# Header_-_Digital_Pot_4131_with_Transisto.net
KiCad netlist of a schematic drawn in EAGLE
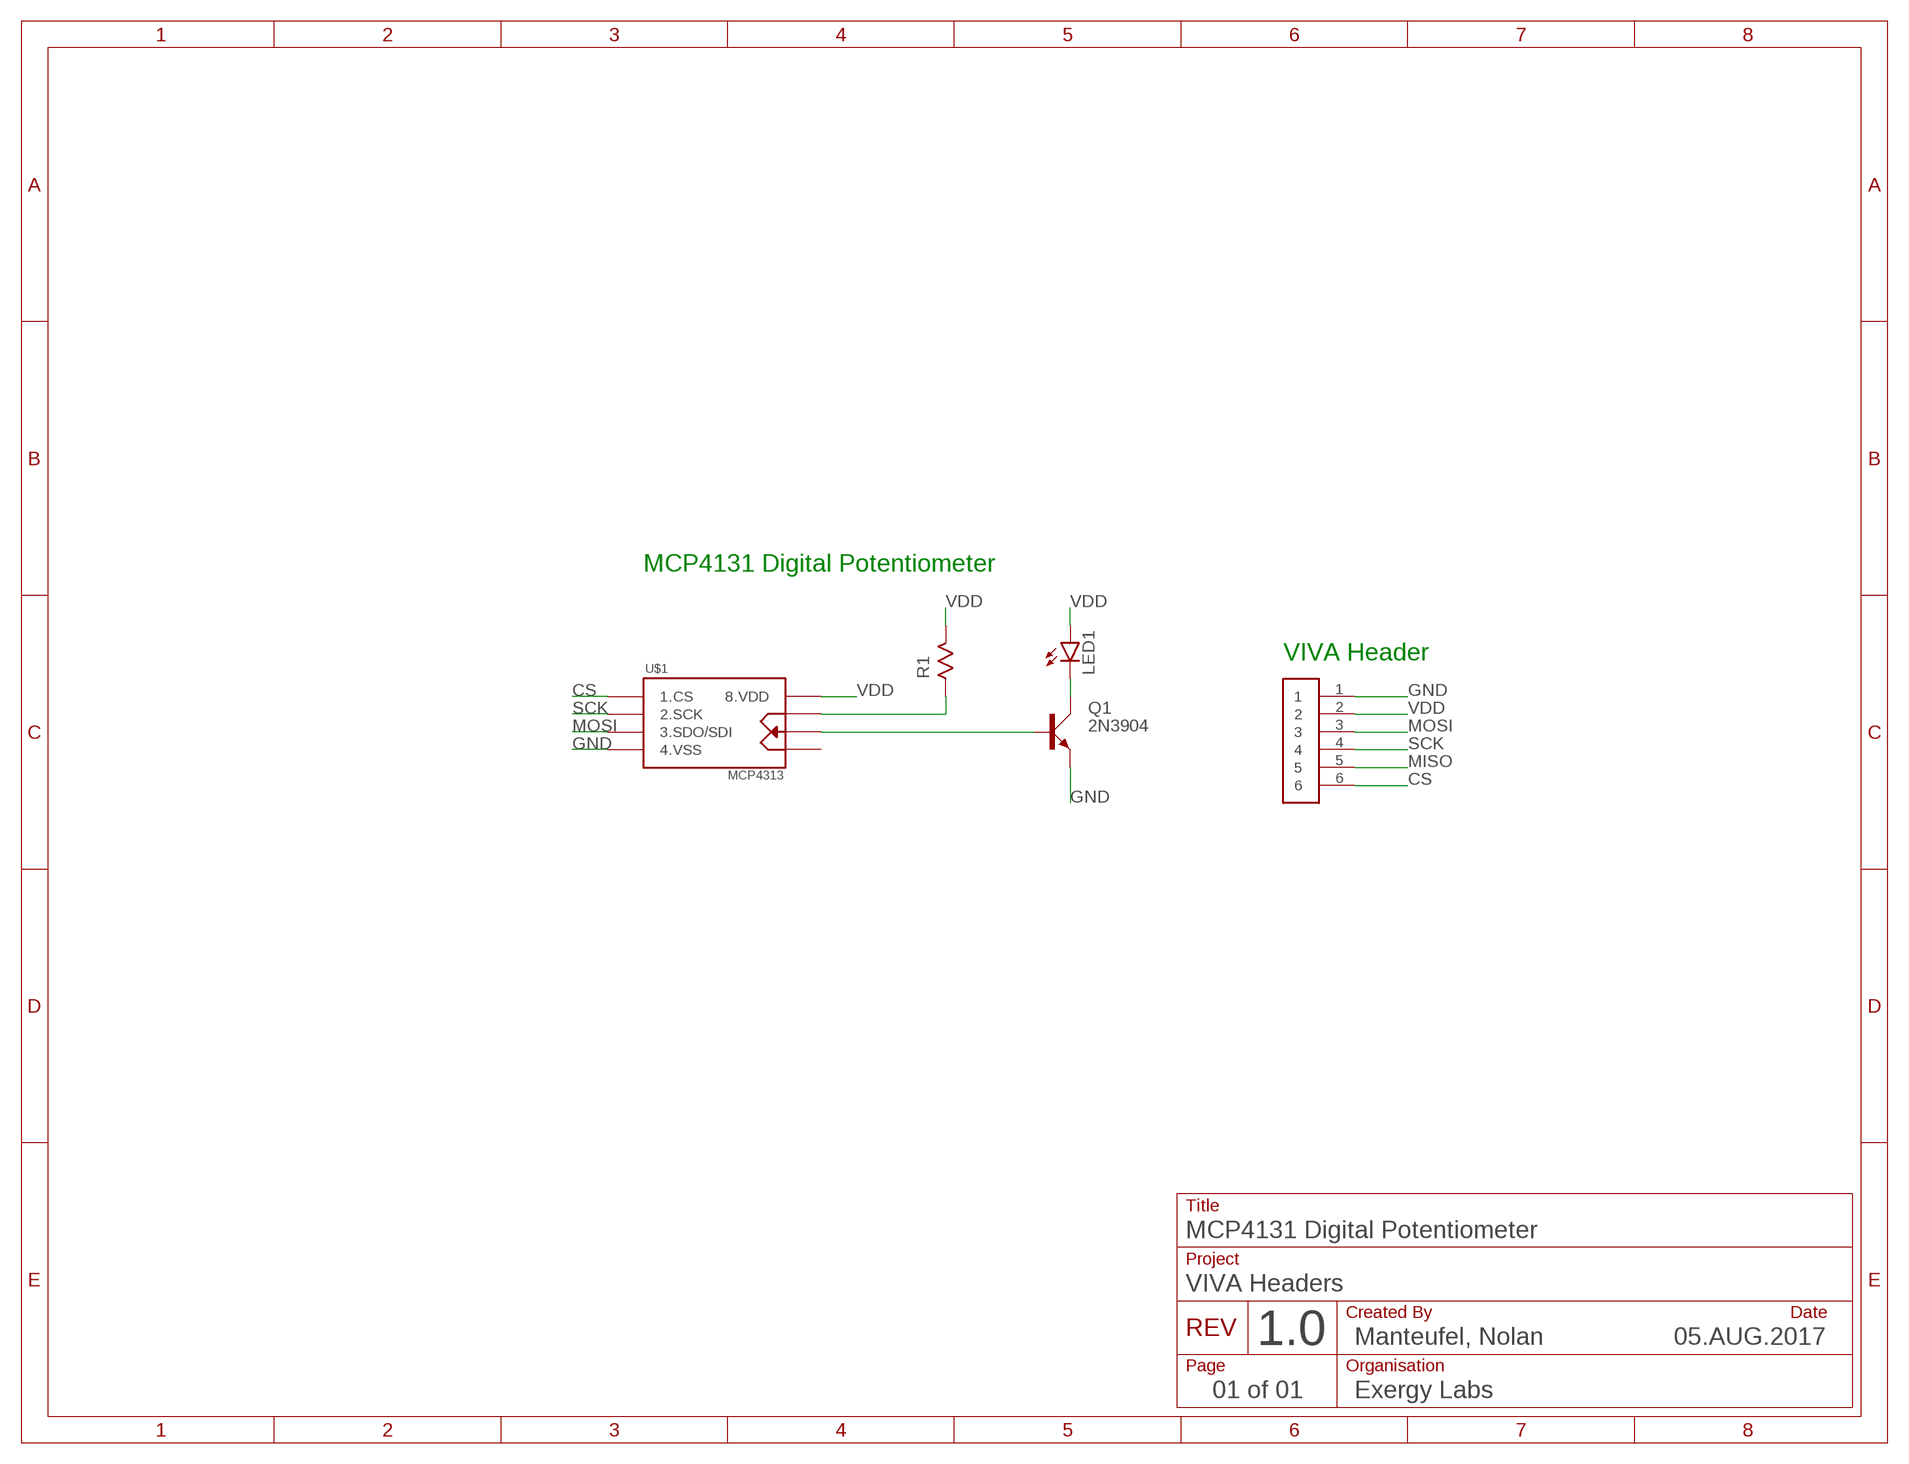
[diagram p0: schematic, sheet 1]

(export (version "E")
  (design (tool "Eeschema 10.0.6"))
  (components
    (comp (ref "LED1")
      (value "LED5MM")
      (footprint "eagle-import:LED5MM")
      (libsource (lib "eagle-import") (part "LED5MM"))
    )
    (comp (ref "Q1")
      (value "2N3904")
      (footprint "eagle-import:TO92-EBC-OVAL")
      (libsource (lib "eagle-import") (part "2N3904TO92-EBC-OVAL"))
    )
    (comp (ref "R1")
      (value "R204-7")
      (footprint "eagle-import:0204_7")
      (libsource (lib "eagle-import") (part "R204-7"))
    )
    (comp (ref "U$1")
      (value "MCP4131")
      (footprint "eagle-import:DIL08")
      (libsource (lib "eagle-import") (part "MCP4131"))
    )
    (comp (ref "U$2")
      (value "PINS_6SQUARE")
      (footprint "eagle-import:PINS_6")
      (libsource (lib "eagle-import") (part "PINS_6SQUARE"))
    )
  )
  (nets
    (net (code "1") (name "/CS") (class "Default")
      (node (ref "U$1") (pin "1") (pinfunction "1.CS_1") (pintype "bidirectional"))
      (node (ref "U$2") (pin "6") (pinfunction "6_6") (pintype "bidirectional"))
    )
    (net (code "2") (name "/GND") (class "Default")
      (node (ref "Q1") (pin "E") (pinfunction "E_E") (pintype "passive"))
      (node (ref "U$1") (pin "4") (pinfunction "4.VSS_4") (pintype "bidirectional"))
      (node (ref "U$2") (pin "1") (pinfunction "1_1") (pintype "bidirectional"))
    )
    (net (code "3") (name "/MISO") (class "Default")
      (node (ref "U$2") (pin "5") (pinfunction "5_5") (pintype "bidirectional"))
    )
    (net (code "4") (name "/MOSI") (class "Default")
      (node (ref "U$1") (pin "3") (pinfunction "3.SDO/SDI_3") (pintype "bidirectional"))
      (node (ref "U$2") (pin "3") (pinfunction "3_3") (pintype "bidirectional"))
    )
    (net (code "5") (name "/SCK") (class "Default")
      (node (ref "U$1") (pin "2") (pinfunction "2.SCK_2") (pintype "bidirectional"))
      (node (ref "U$2") (pin "4") (pinfunction "4_4") (pintype "bidirectional"))
    )
    (net (code "6") (name "/VDD") (class "Default")
      (node (ref "LED1") (pin "A") (pinfunction "A_A") (pintype "passive"))
      (node (ref "R1") (pin "2") (pinfunction "P$2_2") (pintype "bidirectional"))
      (node (ref "U$1") (pin "8") (pinfunction "8.VDD_8") (pintype "bidirectional"))
      (node (ref "U$2") (pin "2") (pinfunction "2_2") (pintype "bidirectional"))
    )
    (net (code "7") (name "Net-(LED1-C)") (class "Default")
      (node (ref "LED1") (pin "K") (pinfunction "C_K") (pintype "passive"))
      (node (ref "Q1") (pin "C") (pinfunction "C_C") (pintype "passive"))
    )
    (net (code "8") (name "Net-(R1-P$1)") (class "Default")
      (node (ref "R1") (pin "1") (pinfunction "P$1_1") (pintype "bidirectional"))
      (node (ref "U$1") (pin "7") (pinfunction "7.P0B_7") (pintype "bidirectional"))
    )
    (net (code "9") (name "Net-(U$1-6.P0W)") (class "Default")
      (node (ref "Q1") (pin "B") (pinfunction "B_B") (pintype "passive"))
      (node (ref "U$1") (pin "6") (pinfunction "6.P0W_6") (pintype "bidirectional"))
    )
    (net (code "10") (name "unconnected-(U$1-5.P0A-Pad5)") (class "Default")
      (node (ref "U$1") (pin "5") (pinfunction "5.P0A_5") (pintype "bidirectional"))
    )
  )
)
